# MCU009A_Connector_IO.net
KiCad netlist of a schematic drawn in Altium Designer
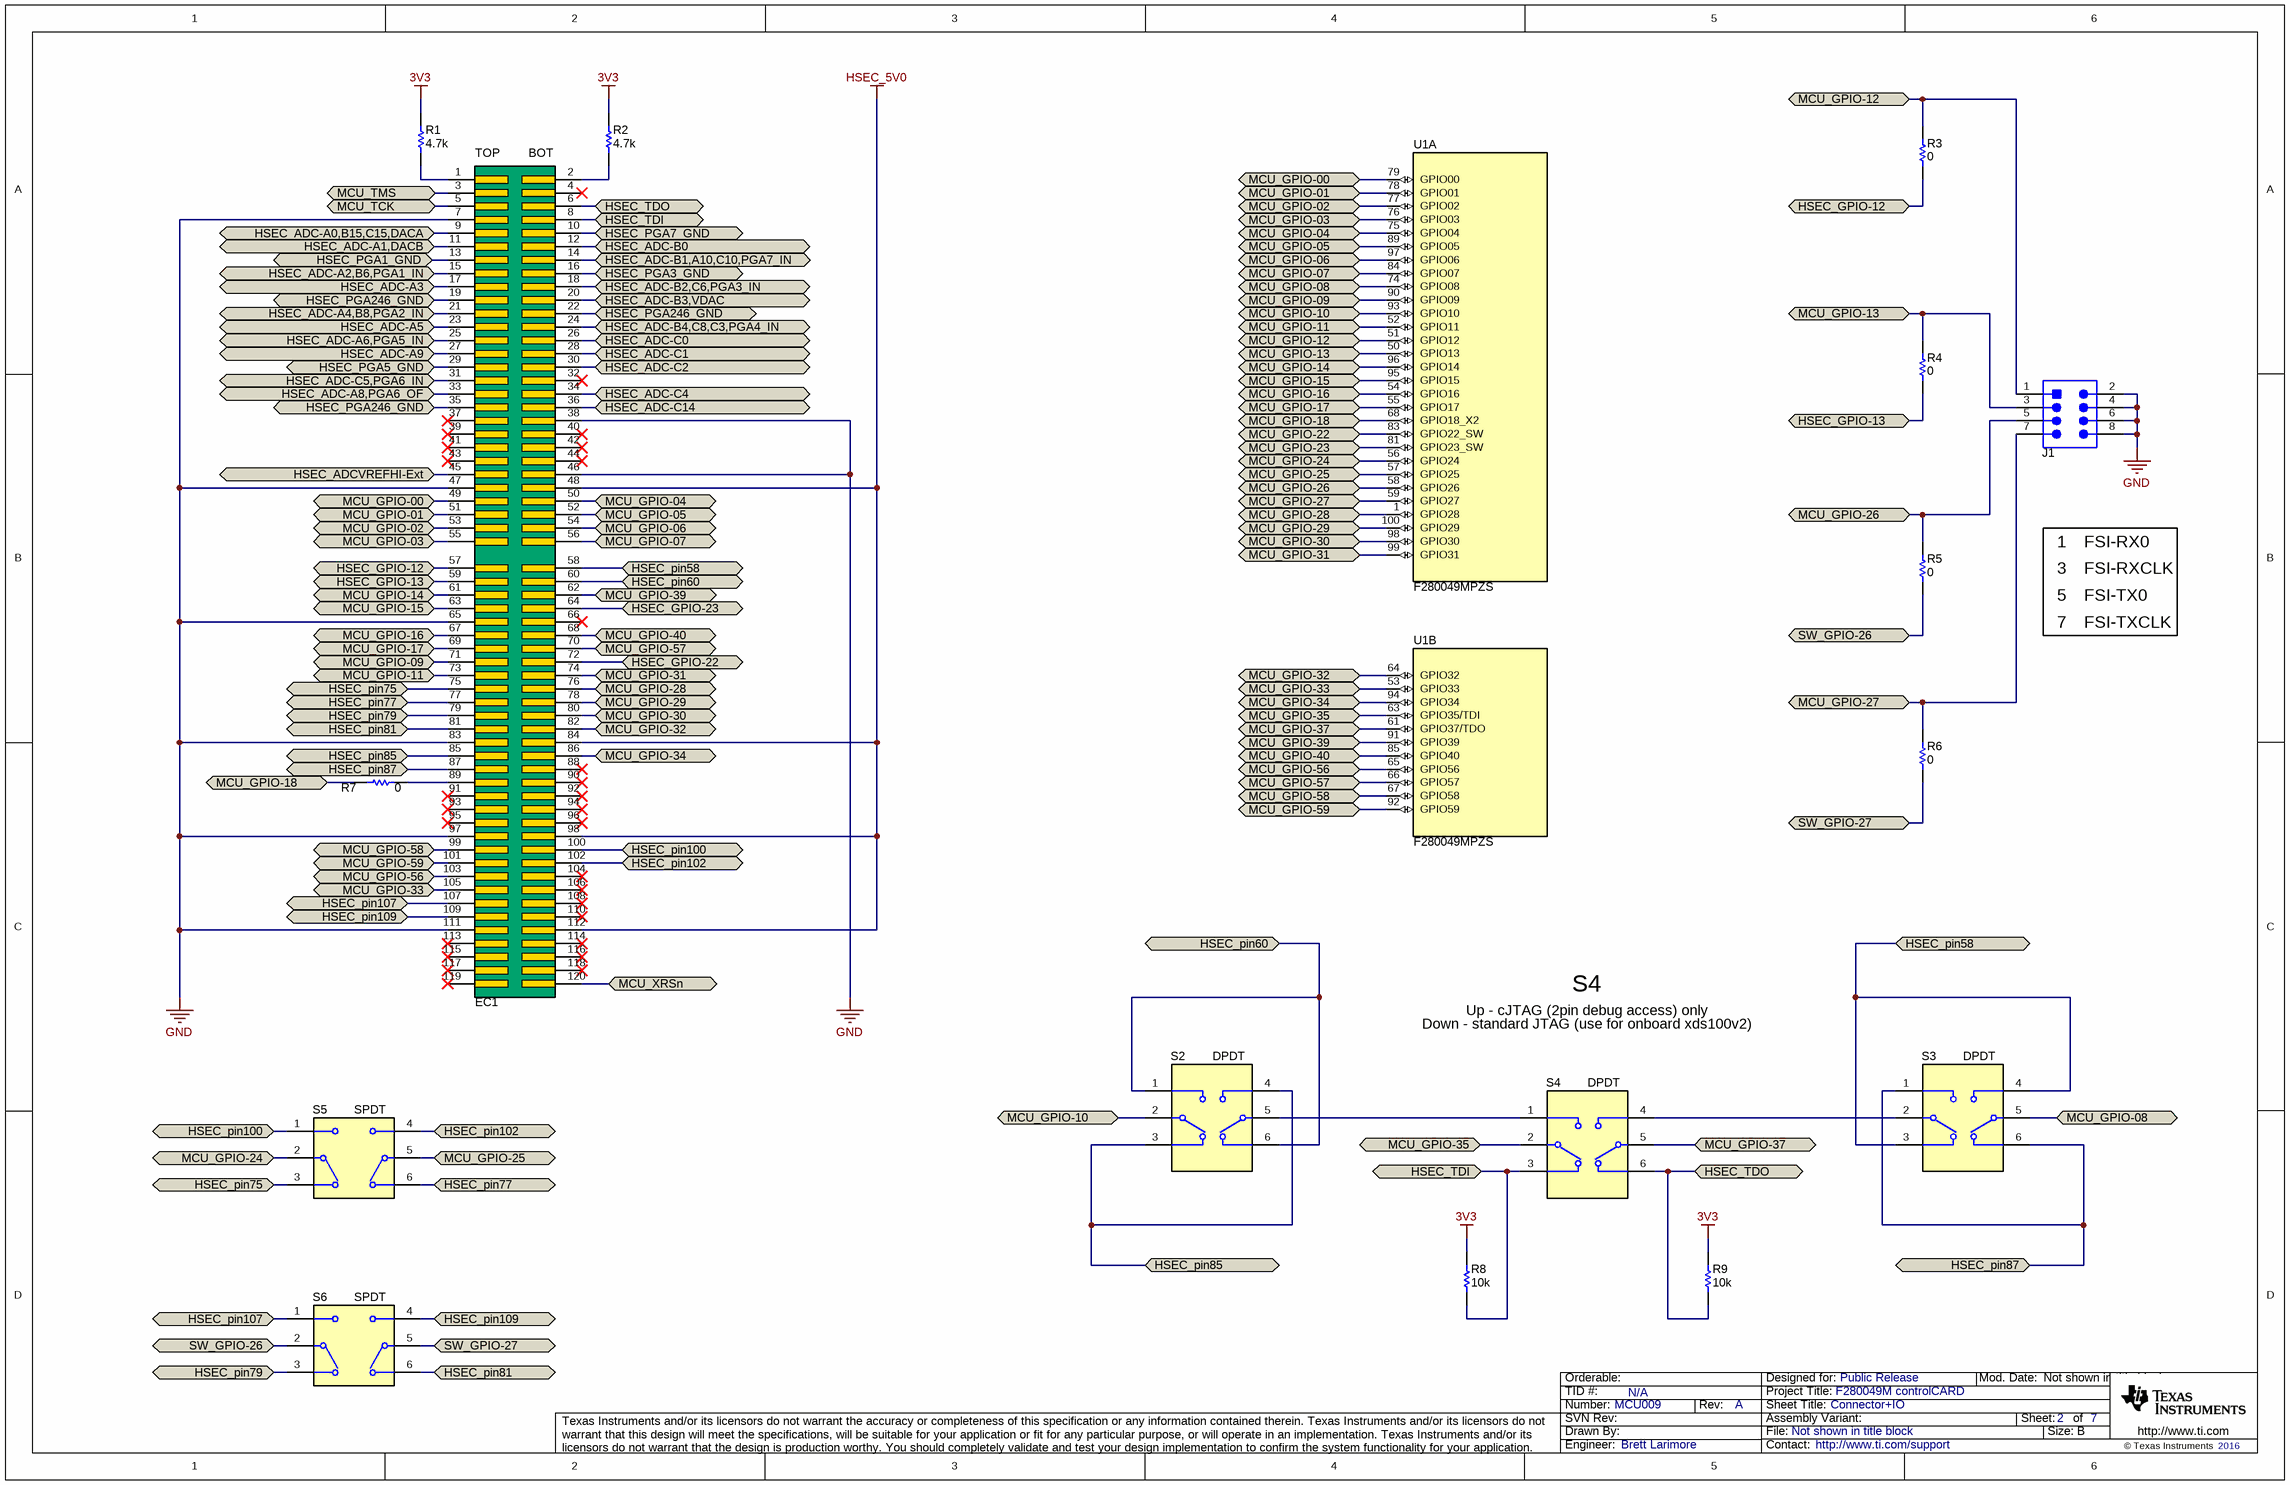
[diagram p0: MCU009A_Connector+IO.SchDoc]

(export (version "E")
  (design (tool "Eeschema 10.0.6"))
  (components
    (comp (ref "EC1")
      (value "controlCARD-120HSEC_Edge")
      (footprint "controlCARD-120HSEC_Edge")
      (description "C2000 controlCARD-120HSEC Edge Connector for Samtec HSEC8-160-01-L-DV-A-BL")
      (fields
        (field (name "MANUFACTURER") "Any")
        (field (name "SYMBOLCREATOR") "a0412235")
        (field (name "PUBLISHER") "Texas Instruments")
      )
      (libsource (lib "Hardware") (part "controlCARD-120HSEC_Edge"))
    )
    (comp (ref "J1")
      (value "TMM-104-01-T-D")
      (footprint "Samtec_TMM-104-01-x-D")
      (description "Header, 2mm, 4x2, Tin, TH")
      (fields
        (field (name "MANUFACTURER") "Samtec")
        (field (name "SYMBOLCREATOR") "a0411947")
        (field (name "PUBLISHER") "Texas Instruments")
      )
      (libsource (lib "Connectors_Samtec1") (part "TMM-104-01-T-D"))
    )
    (comp (ref "R1")
      (value "CRCW04024K70JNED")
      (footprint "0402")
      (description "RES, 4.7 k, 5%, 0.063 W, 0402")
      (fields
        (field (name "VALUEDISPLAYED") "4.7k")
        (field (name "MANUFACTURER") "Vishay-Dale")
        (field (name "PUBLISHER") "Texas Instruments")
      )
      (libsource (lib "Resistor_0402") (part "CRCW04024K70JNED"))
    )
    (comp (ref "R2")
      (value "CRCW04024K70JNED")
      (footprint "0402")
      (description "RES, 4.7 k, 5%, 0.063 W, 0402")
      (fields
        (field (name "VALUEDISPLAYED") "4.7k")
        (field (name "MANUFACTURER") "Vishay-Dale")
        (field (name "PUBLISHER") "Texas Instruments")
      )
      (libsource (lib "Resistor_0402") (part "CRCW04024K70JNED"))
    )
    (comp (ref "R3")
      (value "CRCW06030000Z0EA")
      (footprint "0603")
      (description "RES, 0, 5%, 0.1 W, 0603")
      (fields
        (field (name "VALUEDISPLAYED") "0")
        (field (name "MANUFACTURER") "Vishay-Dale")
        (field (name "PUBLISHER") "Texas Instruments")
      )
      (libsource (lib "Resistor_0603") (part "CRCW06030000Z0EA"))
    )
    (comp (ref "R4")
      (value "CRCW06030000Z0EA")
      (footprint "0603")
      (description "RES, 0, 5%, 0.1 W, 0603")
      (fields
        (field (name "VALUEDISPLAYED") "0")
        (field (name "MANUFACTURER") "Vishay-Dale")
        (field (name "PUBLISHER") "Texas Instruments")
      )
      (libsource (lib "Resistor_0603") (part "CRCW06030000Z0EA"))
    )
    (comp (ref "R5")
      (value "CRCW06030000Z0EA")
      (footprint "0603")
      (description "RES, 0, 5%, 0.1 W, 0603")
      (fields
        (field (name "VALUEDISPLAYED") "0")
        (field (name "MANUFACTURER") "Vishay-Dale")
        (field (name "PUBLISHER") "Texas Instruments")
      )
      (libsource (lib "Resistor_0603") (part "CRCW06030000Z0EA"))
    )
    (comp (ref "R6")
      (value "CRCW06030000Z0EA")
      (footprint "0603")
      (description "RES, 0, 5%, 0.1 W, 0603")
      (fields
        (field (name "VALUEDISPLAYED") "0")
        (field (name "MANUFACTURER") "Vishay-Dale")
        (field (name "PUBLISHER") "Texas Instruments")
      )
      (libsource (lib "Resistor_0603") (part "CRCW06030000Z0EA"))
    )
    (comp (ref "R7")
      (value "CRCW06030000Z0EA")
      (footprint "0603")
      (description "RES, 0, 5%, 0.1 W, 0603")
      (fields
        (field (name "VALUEDISPLAYED") "0")
        (field (name "MANUFACTURER") "Vishay-Dale")
        (field (name "PUBLISHER") "Texas Instruments")
      )
      (libsource (lib "Resistor_0603") (part "CRCW06030000Z0EA"))
    )
    (comp (ref "R8")
      (value "CRCW040210K0JNED")
      (footprint "0402")
      (description "RES, 10 k, 5%, 0.063 W, 0402")
      (fields
        (field (name "VALUEDISPLAYED") "10k")
        (field (name "MANUFACTURER") "Vishay-Dale")
        (field (name "PUBLISHER") "Texas Instruments")
      )
      (libsource (lib "Resistor_0402") (part "CRCW040210K0JNED"))
    )
    (comp (ref "R9")
      (value "CRCW040210K0JNED")
      (footprint "0402")
      (description "RES, 10 k, 5%, 0.063 W, 0402")
      (fields
        (field (name "VALUEDISPLAYED") "10k")
        (field (name "MANUFACTURER") "Vishay-Dale")
        (field (name "PUBLISHER") "Texas Instruments")
      )
      (libsource (lib "Resistor_0402") (part "CRCW040210K0JNED"))
    )
    (comp (ref "S2")
      (value "CAS-220TA")
      (footprint "SW_CAS-220TA")
      (description "SLIDE SWITCH DPDT  .1A, SMT")
      (fields
        (field (name "MANUFACTURER") "Copal Electronics")
        (field (name "CIRCUIT") "DPDT")
        (field (name "SYMBOLCREATOR") "a0411947")
        (field (name "PUBLISHER") "Texas Instruments")
      )
      (libsource (lib "Switches") (part "CAS-220TA"))
    )
    (comp (ref "S3")
      (value "CAS-220TA")
      (footprint "SW_CAS-220TA")
      (description "SLIDE SWITCH DPDT  .1A, SMT")
      (fields
        (field (name "MANUFACTURER") "Copal Electronics")
        (field (name "CIRCUIT") "DPDT")
        (field (name "SYMBOLCREATOR") "a0411947")
        (field (name "PUBLISHER") "Texas Instruments")
      )
      (libsource (lib "Switches") (part "CAS-220TA"))
    )
    (comp (ref "S4")
      (value "CAS-220TA")
      (footprint "SW_CAS-220TA")
      (description "SLIDE SWITCH DPDT  .1A, SMT")
      (fields
        (field (name "MANUFACTURER") "Copal Electronics")
        (field (name "CIRCUIT") "DPDT")
        (field (name "SYMBOLCREATOR") "a0411947")
        (field (name "PUBLISHER") "Texas Instruments")
      )
      (libsource (lib "Switches") (part "CAS-220TA"))
    )
    (comp (ref "S5")
      (value "CAS-D20TA")
      (footprint "SW_CAS-D20TA")
      (description "Switch, Dual SPDT,  2 Pos, 0.1A, 6VDC, SMD")
      (fields
        (field (name "MANUFACTURER") "Copal Electronics")
        (field (name "CIRCUIT") "SPDT")
        (field (name "SYMBOLCREATOR") "Altium")
        (field (name "PUBLISHER") "Texas Instruments")
      )
      (libsource (lib "Switches") (part "CAS-D20TA"))
    )
    (comp (ref "S6")
      (value "CAS-D20TA")
      (footprint "SW_CAS-D20TA")
      (description "Switch, Dual SPDT,  2 Pos, 0.1A, 6VDC, SMD")
      (fields
        (field (name "MANUFACTURER") "Copal Electronics")
        (field (name "CIRCUIT") "SPDT")
        (field (name "SYMBOLCREATOR") "Altium")
        (field (name "PUBLISHER") "Texas Instruments")
      )
      (libsource (lib "Switches") (part "CAS-D20TA"))
    )
    (comp (ref "U1")
      (value "F280049MPZS")
      (footprint "PZ0100A_N")
      (description "Piccolo Microcontroller, PZ0100A (LQFP-100)")
      (fields
        (field (name "MANUFACTURER") "Texas Instruments")
        (field (name "SYMBOLCREATOR") "Altium")
        (field (name "PUBLISHER") "Texas Instruments")
      )
      (libsource (lib "TI_Pre_RTM") (part "F280049MPZS"))
    )
  )
  (nets
    (net (code "1") (name "/HSEC_ADC-A0,B15,C15,DACA") (class "Default")
      (node (ref "EC1") (pin "9") (pinfunction "9_9") (pintype "passive"))
    )
    (net (code "2") (name "/HSEC_ADC-A1,DACB") (class "Default")
      (node (ref "EC1") (pin "11") (pinfunction "11_11") (pintype "passive"))
    )
    (net (code "3") (name "/HSEC_ADC-A2,B6,PGA1_IN") (class "Default")
      (node (ref "EC1") (pin "15") (pinfunction "15_15") (pintype "passive"))
    )
    (net (code "4") (name "/HSEC_ADC-A3") (class "Default")
      (node (ref "EC1") (pin "17") (pinfunction "17_17") (pintype "passive"))
    )
    (net (code "5") (name "/HSEC_ADC-A4,B8,PGA2_IN") (class "Default")
      (node (ref "EC1") (pin "21") (pinfunction "21_21") (pintype "passive"))
    )
    (net (code "6") (name "/HSEC_ADC-A5") (class "Default")
      (node (ref "EC1") (pin "23") (pinfunction "23_23") (pintype "passive"))
    )
    (net (code "7") (name "/HSEC_ADC-A6,PGA5_IN") (class "Default")
      (node (ref "EC1") (pin "25") (pinfunction "25_25") (pintype "passive"))
    )
    (net (code "8") (name "/HSEC_ADC-A8,PGA6_OF") (class "Default")
      (node (ref "EC1") (pin "33") (pinfunction "33_33") (pintype "passive"))
    )
    (net (code "9") (name "/HSEC_ADC-A9") (class "Default")
      (node (ref "EC1") (pin "27") (pinfunction "27_27") (pintype "passive"))
    )
    (net (code "10") (name "/HSEC_ADC-B0") (class "Default")
      (node (ref "EC1") (pin "12") (pinfunction "12_12") (pintype "passive"))
    )
    (net (code "11") (name "/HSEC_ADC-B1,A10,C10,PGA7_IN") (class "Default")
      (node (ref "EC1") (pin "14") (pinfunction "14_14") (pintype "passive"))
    )
    (net (code "12") (name "/HSEC_ADC-B2,C6,PGA3_IN") (class "Default")
      (node (ref "EC1") (pin "18") (pinfunction "18_18") (pintype "passive"))
    )
    (net (code "13") (name "/HSEC_ADC-B3,VDAC") (class "Default")
      (node (ref "EC1") (pin "20") (pinfunction "20_20") (pintype "passive"))
    )
    (net (code "14") (name "/HSEC_ADC-B4,C8,C3,PGA4_IN") (class "Default")
      (node (ref "EC1") (pin "24") (pinfunction "24_24") (pintype "passive"))
    )
    (net (code "15") (name "/HSEC_ADC-C0") (class "Default")
      (node (ref "EC1") (pin "26") (pinfunction "26_26") (pintype "passive"))
    )
    (net (code "16") (name "/HSEC_ADC-C1") (class "Default")
      (node (ref "EC1") (pin "28") (pinfunction "28_28") (pintype "passive"))
    )
    (net (code "17") (name "/HSEC_ADC-C2") (class "Default")
      (node (ref "EC1") (pin "30") (pinfunction "30_30") (pintype "passive"))
    )
    (net (code "18") (name "/HSEC_ADC-C4") (class "Default")
      (node (ref "EC1") (pin "34") (pinfunction "34_34") (pintype "passive"))
    )
    (net (code "19") (name "/HSEC_ADC-C5,PGA6_IN") (class "Default")
      (node (ref "EC1") (pin "31") (pinfunction "31_31") (pintype "passive"))
    )
    (net (code "20") (name "/HSEC_ADC-C14") (class "Default")
      (node (ref "EC1") (pin "36") (pinfunction "36_36") (pintype "passive"))
    )
    (net (code "21") (name "/HSEC_ADCVREFHI-Ext") (class "Default")
      (node (ref "EC1") (pin "45") (pinfunction "45_45") (pintype "passive"))
    )
    (net (code "22") (name "/HSEC_GPIO-12") (class "Default")
      (node (ref "EC1") (pin "57") (pinfunction "57_57") (pintype "passive"))
      (node (ref "R3") (pin "1") (pinfunction "1_1") (pintype "passive"))
    )
    (net (code "23") (name "/HSEC_GPIO-13") (class "Default")
      (node (ref "EC1") (pin "59") (pinfunction "59_59") (pintype "passive"))
      (node (ref "R4") (pin "1") (pinfunction "1_1") (pintype "passive"))
    )
    (net (code "24") (name "/HSEC_GPIO-22") (class "Default")
      (node (ref "EC1") (pin "72") (pinfunction "72_72") (pintype "passive"))
    )
    (net (code "25") (name "/HSEC_GPIO-23") (class "Default")
      (node (ref "EC1") (pin "64") (pinfunction "64_64") (pintype "passive"))
    )
    (net (code "26") (name "/HSEC_PGA1_GND") (class "Default")
      (node (ref "EC1") (pin "13") (pinfunction "13_13") (pintype "passive"))
    )
    (net (code "27") (name "/HSEC_PGA3_GND") (class "Default")
      (node (ref "EC1") (pin "16") (pinfunction "16_16") (pintype "passive"))
    )
    (net (code "28") (name "/HSEC_PGA5_GND") (class "Default")
      (node (ref "EC1") (pin "29") (pinfunction "29_29") (pintype "passive"))
    )
    (net (code "29") (name "/HSEC_PGA7_GND") (class "Default")
      (node (ref "EC1") (pin "10") (pinfunction "10_10") (pintype "passive"))
    )
    (net (code "30") (name "/HSEC_PGA246_GND") (class "Default")
      (node (ref "EC1") (pin "19") (pinfunction "19_19") (pintype "passive"))
      (node (ref "EC1") (pin "22") (pinfunction "22_22") (pintype "passive"))
      (node (ref "EC1") (pin "35") (pinfunction "35_35") (pintype "passive"))
    )
    (net (code "31") (name "/HSEC_TDI") (class "Default")
      (node (ref "EC1") (pin "8") (pinfunction "8_8") (pintype "passive"))
      (node (ref "R8") (pin "1") (pinfunction "1_1") (pintype "passive"))
      (node (ref "S4") (pin "3") (pinfunction "3_3") (pintype "passive"))
    )
    (net (code "32") (name "/HSEC_TDO") (class "Default")
      (node (ref "EC1") (pin "6") (pinfunction "6_6") (pintype "passive"))
      (node (ref "R9") (pin "1") (pinfunction "1_1") (pintype "passive"))
      (node (ref "S4") (pin "6") (pinfunction "6_6") (pintype "passive"))
    )
    (net (code "33") (name "/HSEC_pin58") (class "Default")
      (node (ref "EC1") (pin "58") (pinfunction "58_58") (pintype "passive"))
      (node (ref "S3") (pin "3") (pinfunction "3_3") (pintype "passive"))
      (node (ref "S3") (pin "4") (pinfunction "4_4") (pintype "passive"))
    )
    (net (code "34") (name "/HSEC_pin60") (class "Default")
      (node (ref "EC1") (pin "60") (pinfunction "60_60") (pintype "passive"))
      (node (ref "S2") (pin "1") (pinfunction "1_1") (pintype "passive"))
      (node (ref "S2") (pin "6") (pinfunction "6_6") (pintype "passive"))
    )
    (net (code "35") (name "/HSEC_pin75") (class "Default")
      (node (ref "EC1") (pin "75") (pinfunction "75_75") (pintype "passive"))
      (node (ref "S5") (pin "3") (pinfunction "3_3") (pintype "passive"))
    )
    (net (code "36") (name "/HSEC_pin77") (class "Default")
      (node (ref "EC1") (pin "77") (pinfunction "77_77") (pintype "passive"))
      (node (ref "S5") (pin "6") (pinfunction "6_6") (pintype "passive"))
    )
    (net (code "37") (name "/HSEC_pin79") (class "Default")
      (node (ref "EC1") (pin "79") (pinfunction "79_79") (pintype "passive"))
      (node (ref "S6") (pin "3") (pinfunction "3_3") (pintype "passive"))
    )
    (net (code "38") (name "/HSEC_pin81") (class "Default")
      (node (ref "EC1") (pin "81") (pinfunction "81_81") (pintype "passive"))
      (node (ref "S6") (pin "6") (pinfunction "6_6") (pintype "passive"))
    )
    (net (code "39") (name "/HSEC_pin85") (class "Default")
      (node (ref "EC1") (pin "85") (pinfunction "85_85") (pintype "passive"))
      (node (ref "S2") (pin "3") (pinfunction "3_3") (pintype "passive"))
      (node (ref "S2") (pin "4") (pinfunction "4_4") (pintype "passive"))
    )
    (net (code "40") (name "/HSEC_pin87") (class "Default")
      (node (ref "EC1") (pin "87") (pinfunction "87_87") (pintype "passive"))
      (node (ref "S3") (pin "1") (pinfunction "1_1") (pintype "passive"))
      (node (ref "S3") (pin "6") (pinfunction "6_6") (pintype "passive"))
    )
    (net (code "41") (name "/HSEC_pin100") (class "Default")
      (node (ref "EC1") (pin "100") (pinfunction "100_100") (pintype "passive"))
      (node (ref "S5") (pin "1") (pinfunction "1_1") (pintype "passive"))
    )
    (net (code "42") (name "/HSEC_pin102") (class "Default")
      (node (ref "EC1") (pin "102") (pinfunction "102_102") (pintype "passive"))
      (node (ref "S5") (pin "4") (pinfunction "4_4") (pintype "passive"))
    )
    (net (code "43") (name "/HSEC_pin107") (class "Default")
      (node (ref "EC1") (pin "107") (pinfunction "107_107") (pintype "passive"))
      (node (ref "S6") (pin "1") (pinfunction "1_1") (pintype "passive"))
    )
    (net (code "44") (name "/HSEC_pin109") (class "Default")
      (node (ref "EC1") (pin "109") (pinfunction "109_109") (pintype "passive"))
      (node (ref "S6") (pin "4") (pinfunction "4_4") (pintype "passive"))
    )
    (net (code "45") (name "/MCU_GPIO-00") (class "Default")
      (node (ref "EC1") (pin "49") (pinfunction "49_49") (pintype "passive"))
      (node (ref "U1") (pin "79") (pinfunction "GPIO00_79") (pintype "bidirectional"))
    )
    (net (code "46") (name "/MCU_GPIO-01") (class "Default")
      (node (ref "EC1") (pin "51") (pinfunction "51_51") (pintype "passive"))
      (node (ref "U1") (pin "78") (pinfunction "GPIO01_78") (pintype "bidirectional"))
    )
    (net (code "47") (name "/MCU_GPIO-02") (class "Default")
      (node (ref "EC1") (pin "53") (pinfunction "53_53") (pintype "passive"))
      (node (ref "U1") (pin "77") (pinfunction "GPIO02_77") (pintype "bidirectional"))
    )
    (net (code "48") (name "/MCU_GPIO-03") (class "Default")
      (node (ref "EC1") (pin "55") (pinfunction "55_55") (pintype "passive"))
      (node (ref "U1") (pin "76") (pinfunction "GPIO03_76") (pintype "bidirectional"))
    )
    (net (code "49") (name "/MCU_GPIO-04") (class "Default")
      (node (ref "EC1") (pin "50") (pinfunction "50_50") (pintype "passive"))
      (node (ref "U1") (pin "75") (pinfunction "GPIO04_75") (pintype "bidirectional"))
    )
    (net (code "50") (name "/MCU_GPIO-05") (class "Default")
      (node (ref "EC1") (pin "52") (pinfunction "52_52") (pintype "passive"))
      (node (ref "U1") (pin "89") (pinfunction "GPIO05_89") (pintype "bidirectional"))
    )
    (net (code "51") (name "/MCU_GPIO-06") (class "Default")
      (node (ref "EC1") (pin "54") (pinfunction "54_54") (pintype "passive"))
      (node (ref "U1") (pin "97") (pinfunction "GPIO06_97") (pintype "bidirectional"))
    )
    (net (code "52") (name "/MCU_GPIO-07") (class "Default")
      (node (ref "EC1") (pin "56") (pinfunction "56_56") (pintype "passive"))
      (node (ref "U1") (pin "84") (pinfunction "GPIO07_84") (pintype "bidirectional"))
    )
    (net (code "53") (name "/MCU_GPIO-08") (class "Default")
      (node (ref "S3") (pin "5") (pinfunction "5_5") (pintype "passive"))
      (node (ref "U1") (pin "74") (pinfunction "GPIO08_74") (pintype "bidirectional"))
    )
    (net (code "54") (name "/MCU_GPIO-09") (class "Default")
      (node (ref "EC1") (pin "71") (pinfunction "71_71") (pintype "passive"))
      (node (ref "U1") (pin "90") (pinfunction "GPIO09_90") (pintype "bidirectional"))
    )
    (net (code "55") (name "/MCU_GPIO-10") (class "Default")
      (node (ref "S2") (pin "2") (pinfunction "2_2") (pintype "passive"))
      (node (ref "U1") (pin "93") (pinfunction "GPIO10_93") (pintype "bidirectional"))
    )
    (net (code "56") (name "/MCU_GPIO-11") (class "Default")
      (node (ref "EC1") (pin "73") (pinfunction "73_73") (pintype "passive"))
      (node (ref "U1") (pin "52") (pinfunction "GPIO11_52") (pintype "bidirectional"))
    )
    (net (code "57") (name "/MCU_GPIO-12") (class "Default")
      (node (ref "J1") (pin "1") (pinfunction "1_1") (pintype "passive"))
      (node (ref "R3") (pin "2") (pinfunction "2_2") (pintype "passive"))
      (node (ref "U1") (pin "51") (pinfunction "GPIO12_51") (pintype "bidirectional"))
    )
    (net (code "58") (name "/MCU_GPIO-13") (class "Default")
      (node (ref "J1") (pin "3") (pinfunction "3_3") (pintype "passive"))
      (node (ref "R4") (pin "2") (pinfunction "2_2") (pintype "passive"))
      (node (ref "U1") (pin "50") (pinfunction "GPIO13_50") (pintype "bidirectional"))
    )
    (net (code "59") (name "/MCU_GPIO-14") (class "Default")
      (node (ref "EC1") (pin "61") (pinfunction "61_61") (pintype "passive"))
      (node (ref "U1") (pin "96") (pinfunction "GPIO14_96") (pintype "bidirectional"))
    )
    (net (code "60") (name "/MCU_GPIO-15") (class "Default")
      (node (ref "EC1") (pin "63") (pinfunction "63_63") (pintype "passive"))
      (node (ref "U1") (pin "95") (pinfunction "GPIO15_95") (pintype "bidirectional"))
    )
    (net (code "61") (name "/MCU_GPIO-16") (class "Default")
      (node (ref "EC1") (pin "67") (pinfunction "67_67") (pintype "passive"))
      (node (ref "U1") (pin "54") (pinfunction "GPIO16_54") (pintype "bidirectional"))
    )
    (net (code "62") (name "/MCU_GPIO-17") (class "Default")
      (node (ref "EC1") (pin "69") (pinfunction "69_69") (pintype "passive"))
      (node (ref "U1") (pin "55") (pinfunction "GPIO17_55") (pintype "bidirectional"))
    )
    (net (code "63") (name "/MCU_GPIO-18") (class "Default")
      (node (ref "R7") (pin "2") (pinfunction "2_2") (pintype "passive"))
      (node (ref "U1") (pin "68") (pinfunction "GPIO18_X2_68") (pintype "bidirectional"))
    )
    (net (code "64") (name "/MCU_GPIO-22") (class "Default")
      (node (ref "U1") (pin "83") (pinfunction "GPIO22_SW_83") (pintype "bidirectional"))
    )
    (net (code "65") (name "/MCU_GPIO-23") (class "Default")
      (node (ref "U1") (pin "81") (pinfunction "GPIO23_SW_81") (pintype "bidirectional"))
    )
    (net (code "66") (name "/MCU_GPIO-24") (class "Default")
      (node (ref "S5") (pin "2") (pinfunction "C_2") (pintype "passive"))
      (node (ref "U1") (pin "56") (pinfunction "GPIO24_56") (pintype "bidirectional"))
    )
    (net (code "67") (name "/MCU_GPIO-25") (class "Default")
      (node (ref "S5") (pin "5") (pinfunction "C_5") (pintype "passive"))
      (node (ref "U1") (pin "57") (pinfunction "GPIO25_57") (pintype "bidirectional"))
    )
    (net (code "68") (name "/MCU_GPIO-26") (class "Default")
      (node (ref "J1") (pin "5") (pinfunction "5_5") (pintype "passive"))
      (node (ref "R5") (pin "2") (pinfunction "2_2") (pintype "passive"))
      (node (ref "U1") (pin "58") (pinfunction "GPIO26_58") (pintype "bidirectional"))
    )
    (net (code "69") (name "/MCU_GPIO-27") (class "Default")
      (node (ref "J1") (pin "7") (pinfunction "7_7") (pintype "passive"))
      (node (ref "R6") (pin "2") (pinfunction "2_2") (pintype "passive"))
      (node (ref "U1") (pin "59") (pinfunction "GPIO27_59") (pintype "bidirectional"))
    )
    (net (code "70") (name "/MCU_GPIO-28") (class "Default")
      (node (ref "EC1") (pin "76") (pinfunction "76_76") (pintype "passive"))
      (node (ref "U1") (pin "1") (pinfunction "GPIO28_1") (pintype "bidirectional"))
    )
    (net (code "71") (name "/MCU_GPIO-29") (class "Default")
      (node (ref "EC1") (pin "78") (pinfunction "78_78") (pintype "passive"))
      (node (ref "U1") (pin "100") (pinfunction "GPIO29_100") (pintype "bidirectional"))
    )
    (net (code "72") (name "/MCU_GPIO-30") (class "Default")
      (node (ref "EC1") (pin "80") (pinfunction "80_80") (pintype "passive"))
      (node (ref "U1") (pin "98") (pinfunction "GPIO30_98") (pintype "bidirectional"))
    )
    (net (code "73") (name "/MCU_GPIO-31") (class "Default")
      (node (ref "EC1") (pin "74") (pinfunction "74_74") (pintype "passive"))
      (node (ref "U1") (pin "99") (pinfunction "GPIO31_99") (pintype "bidirectional"))
    )
    (net (code "74") (name "/MCU_GPIO-32") (class "Default")
      (node (ref "EC1") (pin "82") (pinfunction "82_82") (pintype "passive"))
      (node (ref "U1") (pin "64") (pinfunction "GPIO32_64") (pintype "bidirectional"))
    )
    (net (code "75") (name "/MCU_GPIO-33") (class "Default")
      (node (ref "EC1") (pin "105") (pinfunction "105_105") (pintype "passive"))
      (node (ref "U1") (pin "53") (pinfunction "GPIO33_53") (pintype "bidirectional"))
    )
    (net (code "76") (name "/MCU_GPIO-34") (class "Default")
      (node (ref "EC1") (pin "86") (pinfunction "86_86") (pintype "passive"))
      (node (ref "U1") (pin "94") (pinfunction "GPIO34_94") (pintype "bidirectional"))
    )
    (net (code "77") (name "/MCU_GPIO-35") (class "Default")
      (node (ref "S4") (pin "2") (pinfunction "2_2") (pintype "passive"))
      (node (ref "U1") (pin "63") (pinfunction "GPIO35/TDI_63") (pintype "bidirectional"))
    )
    (net (code "78") (name "/MCU_GPIO-37") (class "Default")
      (node (ref "S4") (pin "5") (pinfunction "5_5") (pintype "passive"))
      (node (ref "U1") (pin "61") (pinfunction "GPIO37/TDO_61") (pintype "bidirectional"))
    )
    (net (code "79") (name "/MCU_GPIO-39") (class "Default")
      (node (ref "EC1") (pin "62") (pinfunction "62_62") (pintype "passive"))
      (node (ref "U1") (pin "91") (pinfunction "GPIO39_91") (pintype "bidirectional"))
    )
    (net (code "80") (name "/MCU_GPIO-40") (class "Default")
      (node (ref "EC1") (pin "68") (pinfunction "68_68") (pintype "passive"))
      (node (ref "U1") (pin "85") (pinfunction "GPIO40_85") (pintype "bidirectional"))
    )
    (net (code "81") (name "/MCU_GPIO-56") (class "Default")
      (node (ref "EC1") (pin "103") (pinfunction "103_103") (pintype "passive"))
      (node (ref "U1") (pin "65") (pinfunction "GPIO56_65") (pintype "bidirectional"))
    )
    (net (code "82") (name "/MCU_GPIO-57") (class "Default")
      (node (ref "EC1") (pin "70") (pinfunction "70_70") (pintype "passive"))
      (node (ref "U1") (pin "66") (pinfunction "GPIO57_66") (pintype "bidirectional"))
    )
    (net (code "83") (name "/MCU_GPIO-58") (class "Default")
      (node (ref "EC1") (pin "99") (pinfunction "99_99") (pintype "passive"))
      (node (ref "U1") (pin "67") (pinfunction "GPIO58_67") (pintype "bidirectional"))
    )
    (net (code "84") (name "/MCU_GPIO-59") (class "Default")
      (node (ref "EC1") (pin "101") (pinfunction "101_101") (pintype "passive"))
      (node (ref "U1") (pin "92") (pinfunction "GPIO59_92") (pintype "bidirectional"))
    )
    (net (code "85") (name "/MCU_TCK") (class "Default")
      (node (ref "EC1") (pin "5") (pinfunction "5_5") (pintype "passive"))
    )
    (net (code "86") (name "/MCU_TMS") (class "Default")
      (node (ref "EC1") (pin "3") (pinfunction "3_3") (pintype "passive"))
    )
    (net (code "87") (name "/MCU_XRSn") (class "Default")
      (node (ref "EC1") (pin "120") (pinfunction "120_120") (pintype "passive"))
    )
    (net (code "88") (name "/SW_GPIO-26") (class "Default")
      (node (ref "R5") (pin "1") (pinfunction "1_1") (pintype "passive"))
      (node (ref "S6") (pin "2") (pinfunction "C_2") (pintype "passive"))
    )
    (net (code "89") (name "/SW_GPIO-27") (class "Default")
      (node (ref "R6") (pin "1") (pinfunction "1_1") (pintype "passive"))
      (node (ref "S6") (pin "5") (pinfunction "C_5") (pintype "passive"))
    )
    (net (code "90") (name "3V3") (class "Default")
      (node (ref "R1") (pin "1") (pinfunction "1_1") (pintype "passive"))
      (node (ref "R2") (pin "2") (pinfunction "2_2") (pintype "passive"))
      (node (ref "R8") (pin "2") (pinfunction "2_2") (pintype "passive"))
      (node (ref "R9") (pin "2") (pinfunction "2_2") (pintype "passive"))
    )
    (net (code "91") (name "GND") (class "Default")
      (node (ref "EC1") (pin "111") (pinfunction "111_111") (pintype "passive"))
      (node (ref "EC1") (pin "38") (pinfunction "38_38") (pintype "passive"))
      (node (ref "EC1") (pin "46") (pinfunction "46_46") (pintype "passive"))
      (node (ref "EC1") (pin "47") (pinfunction "47_47") (pintype "passive"))
      (node (ref "EC1") (pin "65") (pinfunction "65_65") (pintype "passive"))
      (node (ref "EC1") (pin "7") (pinfunction "7_7") (pintype "passive"))
      (node (ref "EC1") (pin "83") (pinfunction "83_83") (pintype "passive"))
      (node (ref "EC1") (pin "97") (pinfunction "97_97") (pintype "passive"))
      (node (ref "J1") (pin "2") (pinfunction "2_2") (pintype "passive"))
      (node (ref "J1") (pin "4") (pinfunction "4_4") (pintype "passive"))
      (node (ref "J1") (pin "6") (pinfunction "6_6") (pintype "passive"))
      (node (ref "J1") (pin "8") (pinfunction "8_8") (pintype "passive"))
    )
    (net (code "92") (name "HSEC_5V0") (class "Default")
      (node (ref "EC1") (pin "112") (pinfunction "112_112") (pintype "passive"))
      (node (ref "EC1") (pin "48") (pinfunction "48_48") (pintype "passive"))
      (node (ref "EC1") (pin "84") (pinfunction "84_84") (pintype "passive"))
      (node (ref "EC1") (pin "98") (pinfunction "98_98") (pintype "passive"))
    )
    (net (code "93") (name "Net-(EC1-Pad1)") (class "Default")
      (node (ref "EC1") (pin "1") (pinfunction "1_1") (pintype "passive"))
      (node (ref "R1") (pin "2") (pinfunction "2_2") (pintype "passive"))
    )
    (net (code "94") (name "Net-(EC1-Pad2)") (class "Default")
      (node (ref "EC1") (pin "2") (pinfunction "2_2") (pintype "passive"))
      (node (ref "R2") (pin "1") (pinfunction "1_1") (pintype "passive"))
    )
    (net (code "95") (name "Net-(EC1-Pad89)") (class "Default")
      (node (ref "EC1") (pin "89") (pinfunction "89_89") (pintype "passive"))
      (node (ref "R7") (pin "1") (pinfunction "1_1") (pintype "passive"))
    )
    (net (code "96") (name "Net-(S2-Pad5)") (class "Default")
      (node (ref "S2") (pin "5") (pinfunction "5_5") (pintype "passive"))
      (node (ref "S4") (pin "1") (pinfunction "1_1") (pintype "passive"))
    )
    (net (code "97") (name "Net-(S3-Pad2)") (class "Default")
      (node (ref "S3") (pin "2") (pinfunction "2_2") (pintype "passive"))
      (node (ref "S4") (pin "4") (pinfunction "4_4") (pintype "passive"))
    )
    (net (code "98") (name "unconnected-(EC1-Pad4)") (class "Default")
      (node (ref "EC1") (pin "4") (pinfunction "4_4") (pintype "passive+no_connect"))
    )
    (net (code "99") (name "unconnected-(EC1-Pad32)") (class "Default")
      (node (ref "EC1") (pin "32") (pinfunction "32_32") (pintype "passive+no_connect"))
    )
    (net (code "100") (name "unconnected-(EC1-Pad37)") (class "Default")
      (node (ref "EC1") (pin "37") (pinfunction "37_37") (pintype "passive+no_connect"))
    )
    (net (code "101") (name "unconnected-(EC1-Pad39)") (class "Default")
      (node (ref "EC1") (pin "39") (pinfunction "39_39") (pintype "passive+no_connect"))
    )
    (net (code "102") (name "unconnected-(EC1-Pad40)") (class "Default")
      (node (ref "EC1") (pin "40") (pinfunction "40_40") (pintype "passive+no_connect"))
    )
    (net (code "103") (name "unconnected-(EC1-Pad41)") (class "Default")
      (node (ref "EC1") (pin "41") (pinfunction "41_41") (pintype "passive+no_connect"))
    )
    (net (code "104") (name "unconnected-(EC1-Pad42)") (class "Default")
      (node (ref "EC1") (pin "42") (pinfunction "42_42") (pintype "passive+no_connect"))
    )
    (net (code "105") (name "unconnected-(EC1-Pad43)") (class "Default")
      (node (ref "EC1") (pin "43") (pinfunction "43_43") (pintype "passive+no_connect"))
    )
    (net (code "106") (name "unconnected-(EC1-Pad44)") (class "Default")
      (node (ref "EC1") (pin "44") (pinfunction "44_44") (pintype "passive+no_connect"))
    )
    (net (code "107") (name "unconnected-(EC1-Pad66)") (class "Default")
      (node (ref "EC1") (pin "66") (pinfunction "66_66") (pintype "passive+no_connect"))
    )
    (net (code "108") (name "unconnected-(EC1-Pad88)") (class "Default")
      (node (ref "EC1") (pin "88") (pinfunction "88_88") (pintype "passive+no_connect"))
    )
    (net (code "109") (name "unconnected-(EC1-Pad90)") (class "Default")
      (node (ref "EC1") (pin "90") (pinfunction "90_90") (pintype "passive+no_connect"))
    )
    (net (code "110") (name "unconnected-(EC1-Pad91)") (class "Default")
      (node (ref "EC1") (pin "91") (pinfunction "91_91") (pintype "passive+no_connect"))
    )
    (net (code "111") (name "unconnected-(EC1-Pad92)") (class "Default")
      (node (ref "EC1") (pin "92") (pinfunction "92_92") (pintype "passive+no_connect"))
    )
    (net (code "112") (name "unconnected-(EC1-Pad93)") (class "Default")
      (node (ref "EC1") (pin "93") (pinfunction "93_93") (pintype "passive+no_connect"))
    )
    (net (code "113") (name "unconnected-(EC1-Pad94)") (class "Default")
      (node (ref "EC1") (pin "94") (pinfunction "94_94") (pintype "passive+no_connect"))
    )
    (net (code "114") (name "unconnected-(EC1-Pad95)") (class "Default")
      (node (ref "EC1") (pin "95") (pinfunction "95_95") (pintype "passive+no_connect"))
    )
    (net (code "115") (name "unconnected-(EC1-Pad96)") (class "Default")
      (node (ref "EC1") (pin "96") (pinfunction "96_96") (pintype "passive+no_connect"))
    )
    (net (code "116") (name "unconnected-(EC1-Pad104)") (class "Default")
      (node (ref "EC1") (pin "104") (pinfunction "104_104") (pintype "passive+no_connect"))
    )
    (net (code "117") (name "unconnected-(EC1-Pad106)") (class "Default")
      (node (ref "EC1") (pin "106") (pinfunction "106_106") (pintype "passive+no_connect"))
    )
    (net (code "118") (name "unconnected-(EC1-Pad108)") (class "Default")
      (node (ref "EC1") (pin "108") (pinfunction "108_108") (pintype "passive+no_connect"))
    )
    (net (code "119") (name "unconnected-(EC1-Pad110)") (class "Default")
      (node (ref "EC1") (pin "110") (pinfunction "110_110") (pintype "passive+no_connect"))
    )
    (net (code "120") (name "unconnected-(EC1-Pad113)") (class "Default")
      (node (ref "EC1") (pin "113") (pinfunction "113_113") (pintype "passive+no_connect"))
    )
    (net (code "121") (name "unconnected-(EC1-Pad114)") (class "Default")
      (node (ref "EC1") (pin "114") (pinfunction "114_114") (pintype "passive+no_connect"))
    )
    (net (code "122") (name "unconnected-(EC1-Pad115)") (class "Default")
      (node (ref "EC1") (pin "115") (pinfunction "115_115") (pintype "passive+no_connect"))
    )
    (net (code "123") (name "unconnected-(EC1-Pad116)") (class "Default")
      (node (ref "EC1") (pin "116") (pinfunction "116_116") (pintype "passive+no_connect"))
    )
    (net (code "124") (name "unconnected-(EC1-Pad117)") (class "Default")
      (node (ref "EC1") (pin "117") (pinfunction "117_117") (pintype "passive+no_connect"))
    )
    (net (code "125") (name "unconnected-(EC1-Pad118)") (class "Default")
      (node (ref "EC1") (pin "118") (pinfunction "118_118") (pintype "passive+no_connect"))
    )
    (net (code "126") (name "unconnected-(EC1-Pad119)") (class "Default")
      (node (ref "EC1") (pin "119") (pinfunction "119_119") (pintype "passive+no_connect"))
    )
  )
)
